# USB-NORA-W1_SCHEM_02.net
KiCad netlist of a schematic drawn in Altium Designer
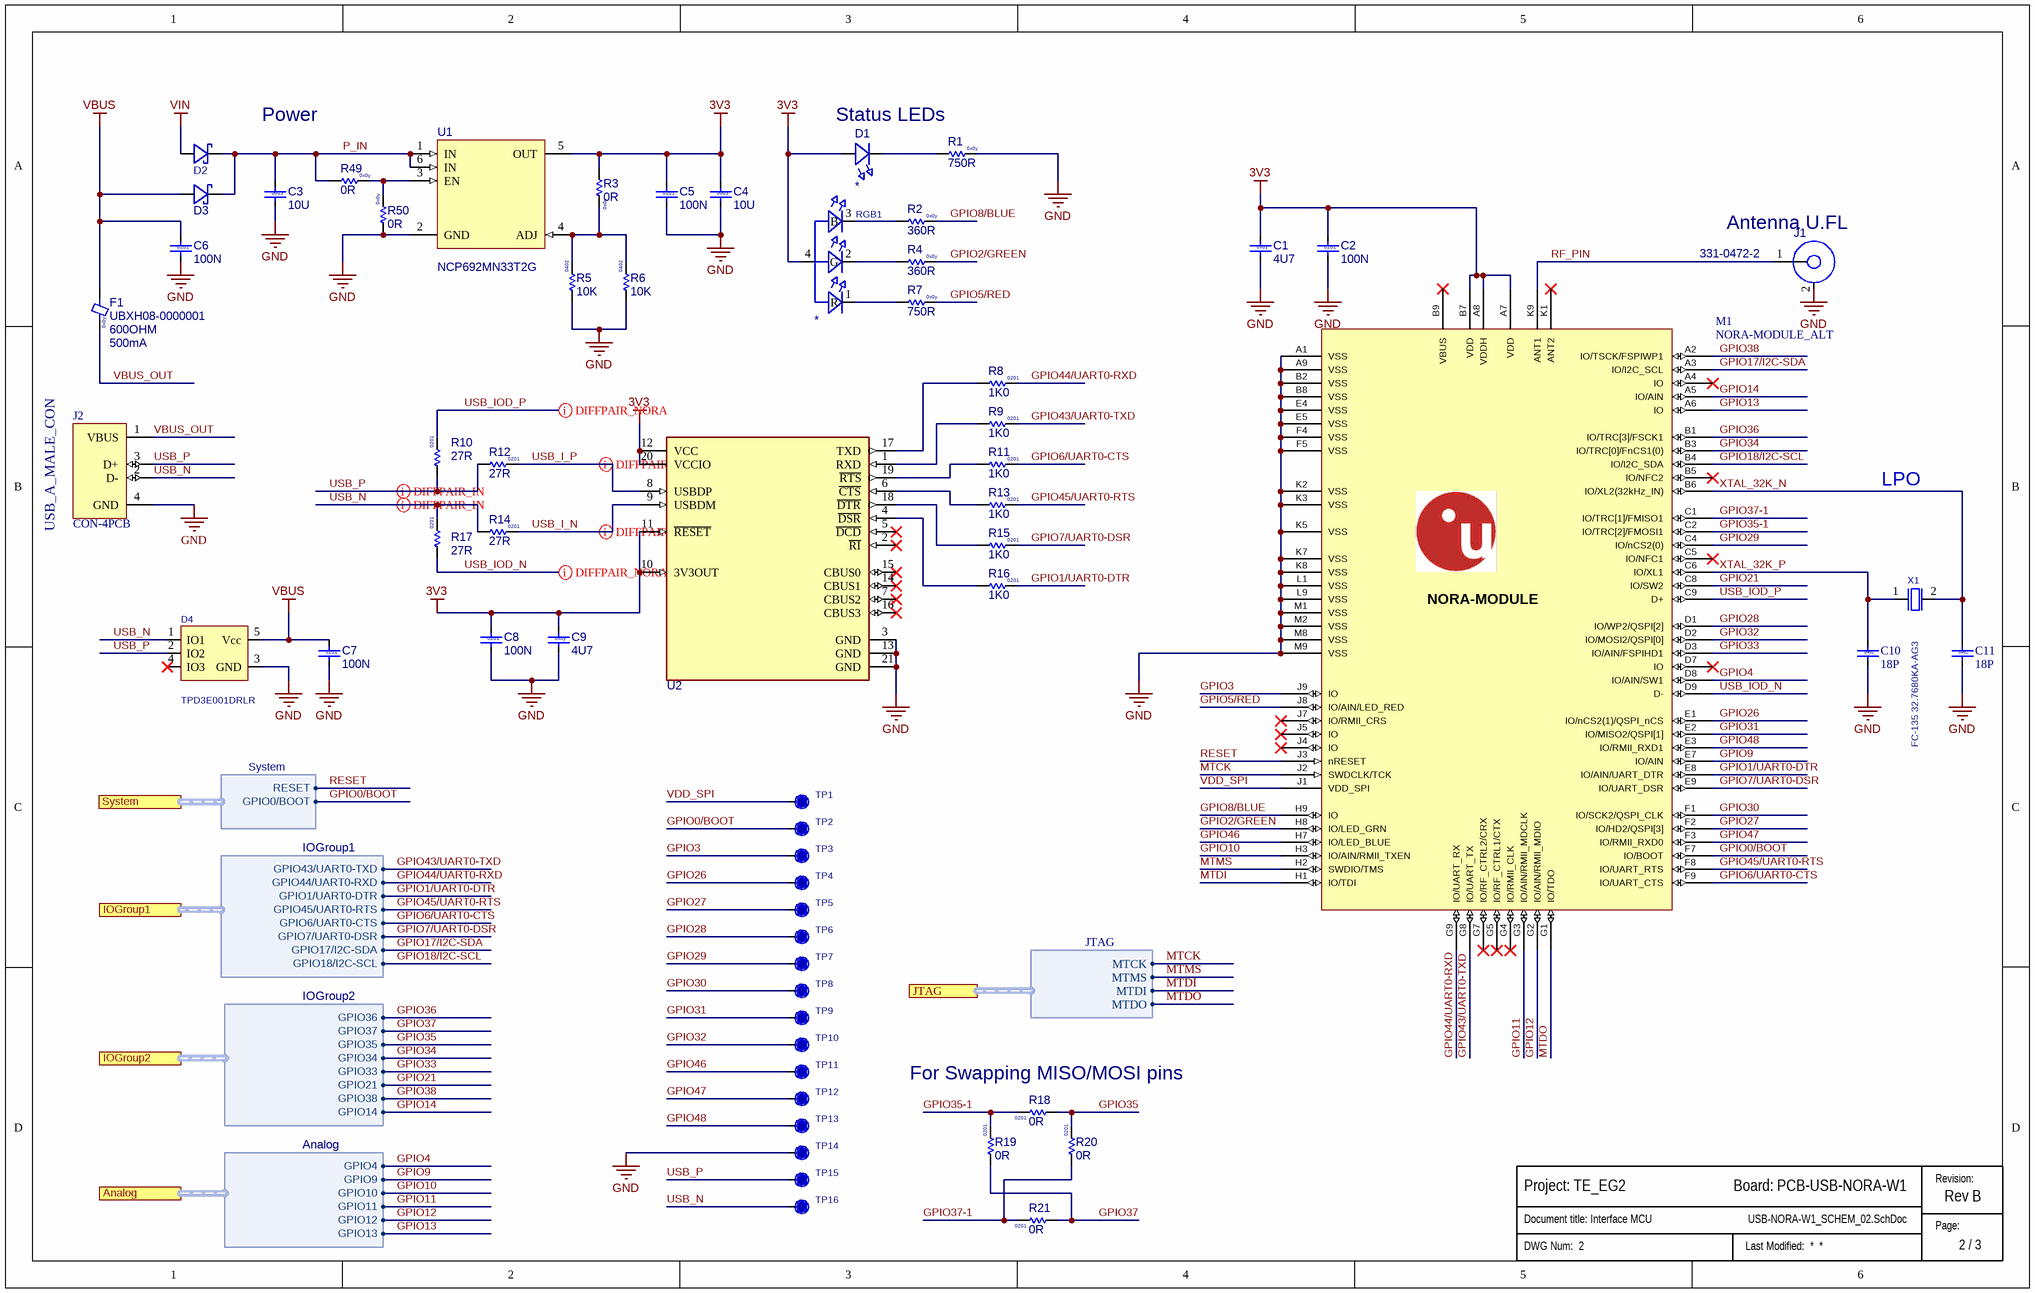
[diagram p0: USB-NORA-W1_SCHEM_02.SchDoc]

(export (version "E")
  (design (tool "Eeschema 10.0.6"))
  (components
    (comp (ref "C1")
      (value "4U7")
      (footprint "Cap 0402 HD")
      (description "CAP CER X5R 0402")
      (fields
        (field (name "SIZE") "0x0y")
        (field (name "PART NUMBER") "UBXH01-0000243")
        (field (name "TOLERANCE") "20%")
        (field (name "EDITOR") "dario.antonaz")
        (field (name "RELEASED BY") "pasquale.scorca")
      )
      (libsource (lib "UBX_Parts_DB_Lib") (part "Cap Chip"))
    )
    (comp (ref "C2")
      (value "100N")
      (footprint "Cap 0201 HD")
      (description "CAP CER X5R 0201 100N 10% 10V")
      (fields
        (field (name "SIZE") "0201")
        (field (name "PART NUMBER") "UBXH01-0000245")
        (field (name "TOLERANCE") "10%")
        (field (name "EDITOR") "dario.antonaz")
        (field (name "RELEASED BY") "jure.podmenik")
      )
      (libsource (lib "UBX_Parts_DB_Lib") (part "Cap Chip"))
    )
    (comp (ref "C3")
      (value "10U")
      (footprint "Cap 0603 HD")
      (description "CAP CER X5R 0603 10U 20% 10V")
      (fields
        (field (name "SIZE") "0603")
        (field (name "PART NUMBER") "UBXH01-0000040")
        (field (name "TOLERANCE") "20%")
        (field (name "EDITOR") "pierpaolo.arban")
        (field (name "RELEASED BY") "matej.budin")
      )
      (libsource (lib "UBX_Parts_DB_Lib") (part "Cap Chip"))
    )
    (comp (ref "C4")
      (value "10U")
      (footprint "Cap 0603 HD")
      (description "CAP CER X5R 0603 10U 20% 10V")
      (fields
        (field (name "SIZE") "0603")
        (field (name "PART NUMBER") "UBXH01-0000040")
        (field (name "TOLERANCE") "20%")
        (field (name "EDITOR") "pierpaolo.arban")
        (field (name "RELEASED BY") "matej.budin")
      )
      (libsource (lib "UBX_Parts_DB_Lib") (part "Cap Chip"))
    )
    (comp (ref "C5")
      (value "100N")
      (footprint "Cap 0201 HD")
      (description "CAP CER X5R 0201 100N 10% 10V")
      (fields
        (field (name "SIZE") "0201")
        (field (name "PART NUMBER") "UBXH01-0000245")
        (field (name "TOLERANCE") "10%")
        (field (name "EDITOR") "dario.antonaz")
        (field (name "RELEASED BY") "jure.podmenik")
      )
      (libsource (lib "UBX_Parts_DB_Lib") (part "Cap Chip"))
    )
    (comp (ref "C6")
      (value "100N")
      (footprint "Cap 0201 HD")
      (description "CAP CER X5R 0201 100N 10% 10V")
      (fields
        (field (name "SIZE") "0201")
        (field (name "PART NUMBER") "UBXH01-0000245")
        (field (name "TOLERANCE") "10%")
        (field (name "EDITOR") "dario.antonaz")
        (field (name "RELEASED BY") "jure.podmenik")
      )
      (libsource (lib "UBX_Parts_DB_Lib") (part "Cap Chip"))
    )
    (comp (ref "C7")
      (value "100N")
      (footprint "Cap 0201 HD")
      (description "CAP CER X5R 0201 100N 10% 10V")
      (fields
        (field (name "SIZE") "0201")
        (field (name "PART NUMBER") "UBXH01-0000245")
        (field (name "TOLERANCE") "10%")
        (field (name "EDITOR") "dario.antonaz")
        (field (name "RELEASED BY") "jure.podmenik")
      )
      (libsource (lib "UBX_Parts_DB_Lib") (part "Cap Chip"))
    )
    (comp (ref "C8")
      (value "100N")
      (footprint "Cap 0201 HD")
      (description "CAP CER X5R 0201 100N 10% 10V")
      (fields
        (field (name "SIZE") "0201")
        (field (name "PART NUMBER") "UBXH01-0000245")
        (field (name "TOLERANCE") "10%")
        (field (name "EDITOR") "dario.antonaz")
        (field (name "RELEASED BY") "jure.podmenik")
      )
      (libsource (lib "UBX_Parts_DB_Lib") (part "Cap Chip"))
    )
    (comp (ref "C9")
      (value "4U7")
      (footprint "Cap 0402 HD")
      (description "CAP CER X5R 0402")
      (fields
        (field (name "SIZE") "0x0y")
        (field (name "PART NUMBER") "UBXH01-0000243")
        (field (name "TOLERANCE") "20%")
        (field (name "EDITOR") "dario.antonaz")
        (field (name "RELEASED BY") "pasquale.scorca")
      )
      (libsource (lib "UBX_Parts_DB_Lib") (part "Cap Chip"))
    )
    (comp (ref "C10")
      (value "18P")
      (footprint "Cap 0402")
      (description "CAP CER C0G 0402 18P 5% 25V")
      (fields
        (field (name "SIZE") "0402")
        (field (name "PART NUMBER") "UBXH01-0004017")
        (field (name "TOLERANCE") "5%")
        (field (name "EDITOR") "doris.zahnd")
        (field (name "RELEASED BY") "daniel.hurni")
      )
      (libsource (lib "UBX_Parts_DB_Lib") (part "Cap Chip"))
    )
    (comp (ref "C11")
      (value "18P")
      (footprint "Cap 0402")
      (description "CAP CER C0G 0402 18P 5% 25V")
      (fields
        (field (name "SIZE") "0402")
        (field (name "PART NUMBER") "UBXH01-0004017")
        (field (name "TOLERANCE") "5%")
        (field (name "EDITOR") "doris.zahnd")
        (field (name "RELEASED BY") "daniel.hurni")
      )
      (libsource (lib "UBX_Parts_DB_Lib") (part "Cap Chip"))
    )
    (comp (ref "D1")
      (value "UBXH11-0000018")
      (footprint "LED-0603")
      (description "LED CHIP 0603 LOW CURRENT OSRAM 0.002A")
      (fields
        (field (name "COLOR") "*")
        (field (name "MANUFACTURER") "Osram")
        (field (name "EDITOR") "johann.furrer")
        (field (name "RELEASED BY") "martin.grasse")
      )
      (libsource (lib "UBX_Parts_DB_Lib") (part "LED_BASE"))
    )
    (comp (ref "D2")
      (value "110-00005")
      (footprint "SOD-123F_U")
      (description "Diode, Schottky, 20V 1A SOD-123F, 340mV Vf @ 1A\nMBR120VLSFT3G")
      (fields (field (name "VOLTAGE") "20V"))
      (libsource (lib "Arena_Parts_DB_Lib") (part "Diode_Schottky"))
    )
    (comp (ref "D3")
      (value "110-00005")
      (footprint "SOD-123F_U")
      (description "Diode, Schottky, 20V 1A SOD-123F, 340mV Vf @ 1A\nMBR120VLSFT3G")
      (fields (field (name "VOLTAGE") "20V"))
      (libsource (lib "Arena_Parts_DB_Lib") (part "Diode_Schottky"))
    )
    (comp (ref "D4")
      (value "110-00018")
      (footprint "SOT-553")
      (description "LOW-CAPACITANCE 3-CHANNEL ESD-PROTECTION ARRAY")
      (fields
        (field (name "MANUFACTURER P/N") "TPD3E001DRLR")
        (field (name "MANUFACTURER") "Texas Instruments")
        (field (name "VOLTAGE") "5V")
      )
      (libsource (lib "Arena_Parts_DB_Lib") (part "TPD3E001"))
    )
    (comp (ref "F1")
      (value "600OHM")
      (footprint "IND 0603 HD")
      (description "FERRITE BEAD, 0603, 600 OHM AT 100MHZ")
      (fields
        (field (name "SIZE") "0x0y")
        (field (name "PART NUMBER") "UBXH08-0000001")
        (field (name "MAX CURRENT") "500mA")
        (field (name "MANUFACTURER") "TDK Corporation")
        (field (name "Comment") "UBXH08-0000001")
        (field (name "EDITOR") "daniel.hurni")
        (field (name "RELEASED BY") "martin.frauchiger")
      )
      (libsource (lib "UBX_Parts_DB_Lib") (part "FB sm"))
    )
    (comp (ref "J1")
      (value "UBXH04-0001026")
      (footprint "U.FL_3Pin")
      (description "CONN HIROSE U.FL SERIES STRAIGHT RECEPTACLE")
      (fields
        (field (name "MANUFACTURER P/N") "331-0472-2")
        (field (name "MANUFACTURER") "Hirose")
        (field (name "EDITOR") "roland.rust")
        (field (name "RELEASED BY") "roland.rust")
      )
      (libsource (lib "UBX_Parts_DB_Lib") (part "CON_Coax_2Pin"))
    )
    (comp (ref "J2")
      (value "CON-4PCB")
      (footprint "USB-A-PCB")
      (description "CONN USB PLUG A TYPE PCB FOOTPRINT")
      (fields (field (name "PART NUMBER") "UBXH04-0000711") (field (name "EDITOR") "aneeb.sohail"))
      (libsource (lib "UBX_Parts_DB_Lib") (part "CON-4PCB"))
    )
    (comp (ref "M1")
      (value "NORA-MODULE_ALT")
      (footprint "NORA:NORA_LGA82R_1430X1040X180_ANT")
      (description "u-blox NORA module generic symbol for use within module designs - alternate version")
      (fields (field (name "PART NUMBER") "NORA") (field (name "MANUFACTURER") "u-blox"))
      (libsource (lib "NORA") (part "NORA-MODULE_ALT"))
    )
    (comp (ref "R1")
      (value "750R")
      (footprint "RES 0402 HD")
      (description "RES THICK FILM CHIP 0402")
      (fields
        (field (name "SIZE") "0x0y")
        (field (name "PART NUMBER") "UBXH18-0008046")
        (field (name "TOLERANCE") "5%")
        (field (name "EDITOR") "jaka.bevk")
        (field (name "RELEASED BY") "erian.bezhani")
      )
      (libsource (lib "UBX_Parts_DB_Lib") (part "Res sm"))
    )
    (comp (ref "R2")
      (value "360R")
      (footprint "RES 0402 HD")
      (description "RES THICK FILM CHIP 0402")
      (fields
        (field (name "SIZE") "0x0y")
        (field (name "PART NUMBER") "UBXH18-0000216")
        (field (name "TOLERANCE") "1%")
        (field (name "EDITOR") "michael.hein")
        (field (name "RELEASED BY") "vasyl.dykyy")
      )
      (libsource (lib "UBX_Parts_DB_Lib") (part "Res sm"))
    )
    (comp (ref "R3")
      (value "0R")
      (footprint "RES 0402 HD")
      (description "RES THICK FILM CHIP 0402")
      (fields
        (field (name "SIZE") "0x0y")
        (field (name "PART NUMBER") "UBXH18-0003002")
        (field (name "TOLERANCE") "0")
        (field (name "EDITOR") "charlotte.biber")
        (field (name "RELEASED BY") "peter.mueller")
      )
      (libsource (lib "UBX_Parts_DB_Lib") (part "Res sm"))
    )
    (comp (ref "R4")
      (value "360R")
      (footprint "RES 0402 HD")
      (description "RES THICK FILM CHIP 0402")
      (fields
        (field (name "SIZE") "0x0y")
        (field (name "PART NUMBER") "UBXH18-0000216")
        (field (name "TOLERANCE") "1%")
        (field (name "EDITOR") "michael.hein")
        (field (name "RELEASED BY") "vasyl.dykyy")
      )
      (libsource (lib "UBX_Parts_DB_Lib") (part "Res sm"))
    )
    (comp (ref "R5")
      (value "10K")
      (footprint "RES 0402 HD")
      (description "RES THICK FILM CHIP 0402 10K 5% 100mW")
      (fields
        (field (name "SIZE") "0402")
        (field (name "PART NUMBER") "UBXH18-0008073")
        (field (name "TOLERANCE") "5%")
        (field (name "EDITOR") "martin.frauchiger")
        (field (name "RELEASED BY") "martin.frauchiger")
      )
      (libsource (lib "UBX_Parts_DB_Lib") (part "Res sm"))
    )
    (comp (ref "R6")
      (value "10K")
      (footprint "RES 0402 HD")
      (description "RES THICK FILM CHIP 0402 10K 5% 100mW")
      (fields
        (field (name "SIZE") "0402")
        (field (name "PART NUMBER") "UBXH18-0008073")
        (field (name "TOLERANCE") "5%")
        (field (name "EDITOR") "martin.frauchiger")
        (field (name "RELEASED BY") "martin.frauchiger")
      )
      (libsource (lib "UBX_Parts_DB_Lib") (part "Res sm"))
    )
    (comp (ref "R7")
      (value "750R")
      (footprint "RES 0402 HD")
      (description "RES THICK FILM CHIP 0402")
      (fields
        (field (name "SIZE") "0x0y")
        (field (name "PART NUMBER") "UBXH18-0008046")
        (field (name "TOLERANCE") "5%")
        (field (name "EDITOR") "jaka.bevk")
        (field (name "RELEASED BY") "erian.bezhani")
      )
      (libsource (lib "UBX_Parts_DB_Lib") (part "Res sm"))
    )
    (comp (ref "R8")
      (value "1K0")
      (footprint "RES 0201 HD")
      (description "RES THICK FILM CHIP 0201 1K0 5% 50mW")
      (fields
        (field (name "SIZE") "0201")
        (field (name "PART NUMBER") "UBXH18-0000007")
        (field (name "TOLERANCE") "5%")
        (field (name "EDITOR") "martin.pilik")
        (field (name "RELEASED BY") "fabrice.bret-dibat")
      )
      (libsource (lib "UBX_Parts_DB_Lib") (part "Res sm"))
    )
    (comp (ref "R9")
      (value "1K0")
      (footprint "RES 0201 HD")
      (description "RES THICK FILM CHIP 0201 1K0 5% 50mW")
      (fields
        (field (name "SIZE") "0201")
        (field (name "PART NUMBER") "UBXH18-0000007")
        (field (name "TOLERANCE") "5%")
        (field (name "EDITOR") "martin.pilik")
        (field (name "RELEASED BY") "fabrice.bret-dibat")
      )
      (libsource (lib "UBX_Parts_DB_Lib") (part "Res sm"))
    )
    (comp (ref "R10")
      (value "27R")
      (footprint "RES 0201 HD")
      (description "RES THICK FILM CHIP 0201 27R 5% 50mW")
      (fields
        (field (name "SIZE") "0201")
        (field (name "PART NUMBER") "UBXH18-0000470")
        (field (name "TOLERANCE") "5%")
        (field (name "EDITOR") "alex.claville")
        (field (name "RELEASED BY") "andre.pick")
      )
      (libsource (lib "UBX_Parts_DB_Lib") (part "Res sm"))
    )
    (comp (ref "R11")
      (value "1K0")
      (footprint "RES 0201 HD")
      (description "RES THICK FILM CHIP 0201 1K0 5% 50mW")
      (fields
        (field (name "SIZE") "0201")
        (field (name "PART NUMBER") "UBXH18-0000007")
        (field (name "TOLERANCE") "5%")
        (field (name "EDITOR") "martin.pilik")
        (field (name "RELEASED BY") "fabrice.bret-dibat")
      )
      (libsource (lib "UBX_Parts_DB_Lib") (part "Res sm"))
    )
    (comp (ref "R12")
      (value "27R")
      (footprint "RES 0201 HD")
      (description "RES THICK FILM CHIP 0201 27R 5% 50mW")
      (fields
        (field (name "SIZE") "0201")
        (field (name "PART NUMBER") "UBXH18-0000470")
        (field (name "TOLERANCE") "5%")
        (field (name "EDITOR") "alex.claville")
        (field (name "RELEASED BY") "andre.pick")
      )
      (libsource (lib "UBX_Parts_DB_Lib") (part "Res sm"))
    )
    (comp (ref "R13")
      (value "1K0")
      (footprint "RES 0201 HD")
      (description "RES THICK FILM CHIP 0201 1K0 5% 50mW")
      (fields
        (field (name "SIZE") "0201")
        (field (name "PART NUMBER") "UBXH18-0000007")
        (field (name "TOLERANCE") "5%")
        (field (name "EDITOR") "martin.pilik")
        (field (name "RELEASED BY") "fabrice.bret-dibat")
      )
      (libsource (lib "UBX_Parts_DB_Lib") (part "Res sm"))
    )
    (comp (ref "R14")
      (value "27R")
      (footprint "RES 0201 HD")
      (description "RES THICK FILM CHIP 0201 27R 5% 50mW")
      (fields
        (field (name "SIZE") "0201")
        (field (name "PART NUMBER") "UBXH18-0000470")
        (field (name "TOLERANCE") "5%")
        (field (name "EDITOR") "alex.claville")
        (field (name "RELEASED BY") "andre.pick")
      )
      (libsource (lib "UBX_Parts_DB_Lib") (part "Res sm"))
    )
    (comp (ref "R15")
      (value "1K0")
      (footprint "RES 0201 HD")
      (description "RES THICK FILM CHIP 0201 1K0 5% 50mW")
      (fields
        (field (name "SIZE") "0201")
        (field (name "PART NUMBER") "UBXH18-0000007")
        (field (name "TOLERANCE") "5%")
        (field (name "EDITOR") "martin.pilik")
        (field (name "RELEASED BY") "fabrice.bret-dibat")
      )
      (libsource (lib "UBX_Parts_DB_Lib") (part "Res sm"))
    )
    (comp (ref "R16")
      (value "1K0")
      (footprint "RES 0201 HD")
      (description "RES THICK FILM CHIP 0201 1K0 5% 50mW")
      (fields
        (field (name "SIZE") "0201")
        (field (name "PART NUMBER") "UBXH18-0000007")
        (field (name "TOLERANCE") "5%")
        (field (name "EDITOR") "martin.pilik")
        (field (name "RELEASED BY") "fabrice.bret-dibat")
      )
      (libsource (lib "UBX_Parts_DB_Lib") (part "Res sm"))
    )
    (comp (ref "R17")
      (value "27R")
      (footprint "RES 0201 HD")
      (description "RES THICK FILM CHIP 0201 27R 5% 50mW")
      (fields
        (field (name "SIZE") "0201")
        (field (name "PART NUMBER") "UBXH18-0000470")
        (field (name "TOLERANCE") "5%")
        (field (name "EDITOR") "alex.claville")
        (field (name "RELEASED BY") "andre.pick")
      )
      (libsource (lib "UBX_Parts_DB_Lib") (part "Res sm"))
    )
    (comp (ref "R18")
      (value "0R")
      (footprint "RES 0201 HD")
      (description "RES THICK FILM CHIP 0201 0R 0 500mA")
      (fields
        (field (name "SIZE") "0201")
        (field (name "PART NUMBER") "UBXH18-0003003")
        (field (name "TOLERANCE") "0")
        (field (name "EDITOR") "martin.pilik")
        (field (name "RELEASED BY") "fabrice.bret-dibat")
      )
      (libsource (lib "") (part "Res sm_1"))
    )
    (comp (ref "R19")
      (value "0R")
      (footprint "RES 0201 HD")
      (description "RES THICK FILM CHIP 0201 0R 0 500mA")
      (fields
        (field (name "SIZE") "0201")
        (field (name "PART NUMBER") "UBXH18-0003003")
        (field (name "TOLERANCE") "0")
        (field (name "EDITOR") "martin.pilik")
        (field (name "RELEASED BY") "fabrice.bret-dibat")
      )
      (libsource (lib "UBX_Parts_DB_Lib") (part "Res sm"))
    )
    (comp (ref "R20")
      (value "0R")
      (footprint "RES 0201 HD")
      (description "RES THICK FILM CHIP 0201 0R 0 500mA")
      (fields
        (field (name "SIZE") "0201")
        (field (name "PART NUMBER") "UBXH18-0003003")
        (field (name "TOLERANCE") "0")
        (field (name "EDITOR") "martin.pilik")
        (field (name "RELEASED BY") "fabrice.bret-dibat")
      )
      (libsource (lib "UBX_Parts_DB_Lib") (part "Res sm"))
    )
    (comp (ref "R21")
      (value "0R")
      (footprint "RES 0201 HD")
      (description "RES THICK FILM CHIP 0201 0R 0 500mA")
      (fields
        (field (name "SIZE") "0201")
        (field (name "PART NUMBER") "UBXH18-0003003")
        (field (name "TOLERANCE") "0")
        (field (name "EDITOR") "martin.pilik")
        (field (name "RELEASED BY") "fabrice.bret-dibat")
      )
      (libsource (lib "") (part "Res sm_1"))
    )
    (comp (ref "R49")
      (value "0R")
      (footprint "RES 0402 HD")
      (description "RES THICK FILM CHIP 0402")
      (fields
        (field (name "SIZE") "0x0y")
        (field (name "PART NUMBER") "UBXH18-0003002")
        (field (name "TOLERANCE") "0")
        (field (name "EDITOR") "charlotte.biber")
        (field (name "RELEASED BY") "peter.mueller")
      )
      (libsource (lib "UBX_Parts_DB_Lib") (part "Res sm"))
    )
    (comp (ref "R50")
      (value "0R")
      (footprint "RES 0402 HD")
      (description "RES THICK FILM CHIP 0402")
      (fields
        (field (name "SIZE") "0x0y")
        (field (name "PART NUMBER") "UBXH18-0003002")
        (field (name "TOLERANCE") "0")
        (field (name "EDITOR") "charlotte.biber")
        (field (name "RELEASED BY") "peter.mueller")
      )
      (libsource (lib "UBX_Parts_DB_Lib") (part "Res sm"))
    )
    (comp (ref "RGB1")
      (value "115-00026")
      (footprint "LED_1616")
      (description "LED RGB SMT 0606")
      (fields (field (name "COLOR") "*") (field (name "VOLTAGE") "None"))
      (libsource (lib "Arena_Parts_DB_Lib") (part "LED_RGB_CA_4"))
    )
    (comp (ref "TP1")
      (value "TP")
      (footprint "TP10R")
      (description "Testpoint, Round 1.0mm Dia")
      (fields
        (field (name "PART NUMBER") "TP10R")
        (field (name "ADDED BY") "Jeremy D")
        (field (name "CHECKED BY") "Paul B")
      )
      (libsource (lib "LEGACY_Rigado_AltiumLib") (part "TP_R"))
    )
    (comp (ref "TP2")
      (value "TP")
      (footprint "TP10R")
      (description "Testpoint, Round 1.0mm Dia")
      (fields
        (field (name "PART NUMBER") "TP10R")
        (field (name "ADDED BY") "Jeremy D")
        (field (name "CHECKED BY") "Paul B")
      )
      (libsource (lib "LEGACY_Rigado_AltiumLib") (part "TP_R"))
    )
    (comp (ref "TP3")
      (value "TP")
      (footprint "TP10R")
      (description "Testpoint, Round 1.0mm Dia")
      (fields
        (field (name "PART NUMBER") "TP10R")
        (field (name "ADDED BY") "Jeremy D")
        (field (name "CHECKED BY") "Paul B")
      )
      (libsource (lib "LEGACY_Rigado_AltiumLib") (part "TP_R"))
    )
    (comp (ref "TP4")
      (value "TP")
      (footprint "TP10R")
      (description "Testpoint, Round 1.0mm Dia")
      (fields
        (field (name "PART NUMBER") "TP10R")
        (field (name "ADDED BY") "Jeremy D")
        (field (name "CHECKED BY") "Paul B")
      )
      (libsource (lib "LEGACY_Rigado_AltiumLib") (part "TP_R"))
    )
    (comp (ref "TP5")
      (value "TP")
      (footprint "TP10R")
      (description "Testpoint, Round 1.0mm Dia")
      (fields
        (field (name "PART NUMBER") "TP10R")
        (field (name "ADDED BY") "Jeremy D")
        (field (name "CHECKED BY") "Paul B")
      )
      (libsource (lib "LEGACY_Rigado_AltiumLib") (part "TP_R"))
    )
    (comp (ref "TP6")
      (value "TP")
      (footprint "TP10R")
      (description "Testpoint, Round 1.0mm Dia")
      (fields
        (field (name "PART NUMBER") "TP10R")
        (field (name "ADDED BY") "Jeremy D")
        (field (name "CHECKED BY") "Paul B")
      )
      (libsource (lib "LEGACY_Rigado_AltiumLib") (part "TP_R"))
    )
    (comp (ref "TP7")
      (value "TP")
      (footprint "TP10R")
      (description "Testpoint, Round 1.0mm Dia")
      (fields
        (field (name "PART NUMBER") "TP10R")
        (field (name "ADDED BY") "Jeremy D")
        (field (name "CHECKED BY") "Paul B")
      )
      (libsource (lib "LEGACY_Rigado_AltiumLib") (part "TP_R"))
    )
    (comp (ref "TP8")
      (value "TP")
      (footprint "TP10R")
      (description "Testpoint, Round 1.0mm Dia")
      (fields
        (field (name "PART NUMBER") "TP10R")
        (field (name "ADDED BY") "Jeremy D")
        (field (name "CHECKED BY") "Paul B")
      )
      (libsource (lib "LEGACY_Rigado_AltiumLib") (part "TP_R"))
    )
    (comp (ref "TP9")
      (value "TP")
      (footprint "TP10R")
      (description "Testpoint, Round 1.0mm Dia")
      (fields
        (field (name "PART NUMBER") "TP10R")
        (field (name "ADDED BY") "Jeremy D")
        (field (name "CHECKED BY") "Paul B")
      )
      (libsource (lib "LEGACY_Rigado_AltiumLib") (part "TP_R"))
    )
    (comp (ref "TP10")
      (value "TP")
      (footprint "TP10R")
      (description "Testpoint, Round 1.0mm Dia")
      (fields
        (field (name "PART NUMBER") "TP10R")
        (field (name "ADDED BY") "Jeremy D")
        (field (name "CHECKED BY") "Paul B")
      )
      (libsource (lib "LEGACY_Rigado_AltiumLib") (part "TP_R"))
    )
    (comp (ref "TP11")
      (value "TP")
      (footprint "TP10R")
      (description "Testpoint, Round 1.0mm Dia")
      (fields
        (field (name "PART NUMBER") "TP10R")
        (field (name "ADDED BY") "Jeremy D")
        (field (name "CHECKED BY") "Paul B")
      )
      (libsource (lib "LEGACY_Rigado_AltiumLib") (part "TP_R"))
    )
    (comp (ref "TP12")
      (value "TP")
      (footprint "TP10R")
      (description "Testpoint, Round 1.0mm Dia")
      (fields
        (field (name "PART NUMBER") "TP10R")
        (field (name "ADDED BY") "Jeremy D")
        (field (name "CHECKED BY") "Paul B")
      )
      (libsource (lib "LEGACY_Rigado_AltiumLib") (part "TP_R"))
    )
    (comp (ref "TP13")
      (value "TP")
      (footprint "TP10R")
      (description "Testpoint, Round 1.0mm Dia")
      (fields
        (field (name "PART NUMBER") "TP10R")
        (field (name "ADDED BY") "Jeremy D")
        (field (name "CHECKED BY") "Paul B")
      )
      (libsource (lib "LEGACY_Rigado_AltiumLib") (part "TP_R"))
    )
    (comp (ref "TP14")
      (value "TP")
      (footprint "TP10R")
      (description "Testpoint, Round 1.0mm Dia")
      (fields
        (field (name "PART NUMBER") "TP10R")
        (field (name "ADDED BY") "Jeremy D")
        (field (name "CHECKED BY") "Paul B")
      )
      (libsource (lib "LEGACY_Rigado_AltiumLib") (part "TP_R"))
    )
    (comp (ref "TP15")
      (value "TP")
      (footprint "TP10R")
      (description "Testpoint, Round 1.0mm Dia")
      (fields
        (field (name "PART NUMBER") "TP10R")
        (field (name "ADDED BY") "Jeremy D")
        (field (name "CHECKED BY") "Paul B")
      )
      (libsource (lib "LEGACY_Rigado_AltiumLib") (part "TP_R"))
    )
    (comp (ref "TP16")
      (value "TP")
      (footprint "TP10R")
      (description "Testpoint, Round 1.0mm Dia")
      (fields
        (field (name "PART NUMBER") "TP10R")
        (field (name "ADDED BY") "Jeremy D")
        (field (name "CHECKED BY") "Paul B")
      )
      (libsource (lib "LEGACY_Rigado_AltiumLib") (part "TP_R"))
    )
    (comp (ref "U1")
      (value "NCP692MN33T2G")
      (footprint "DFN-PSON.1P3X3-7pin_HS-7N")
      (description "LOW DROPOUT REGULATOR ON SEMICONDUCTOR NCP692MN33T2G 6DFN 3.3V 6V 1A")
      (fields
        (field (name "PART NUMBER") "UBXH12-0000459")
        (field (name "MANUFACTURER") "ON Semiconductor")
        (field (name "EDITOR") "hakan.ekfors")
        (field (name "RELEASED BY") "markus.wejrot")
      )
      (libsource (lib "UBX_Parts_DB_Lib") (part "NCP692MN33T2G"))
    )
    (comp (ref "U2")
      (value "FT231XQ-R")
      (footprint "QFN_5x5_FT231XQ")
      (description "FTDI USB TO SERIAL FULL UART INTERFACE QFN20")
      (fields
        (field (name "PART NUMBER") "UBXH10-0000054")
        (field (name "MANUFACTURER") "FTDI Future Technology Devices International")
        (field (name "EDITOR") "adam.johansson")
      )
      (libsource (lib "UBX_Parts_DB_Lib") (part "FT231XQ-R"))
    )
    (comp (ref "X1")
      (value "100-00005")
      (footprint "XTAL_3215")
      (description "XTAL, 2Pin, 32.768kHz, 7pF 20ppm")
      (fields (field (name "MANUFACTURER P/N") "FC-135 32.7680KA-AG3") (field (name "MANUFACTURER") "Epson"))
      (libsource (lib "Arena_Parts_DB_Lib") (part "XTAL_2Pin"))
    )
  )
  (nets
    (net (code "7") (name "/GPIO0{slash}BOOT") (class "Default")
      (node (ref "M1") (pin "F7") (pinfunction "IO/BOOT_F7") (pintype "bidirectional"))
      (node (ref "TP2") (pin "1") (pintype "passive"))
    )
    (net (code "8") (name "/GPIO1{slash}UART0-DTR") (class "Default")
      (node (ref "M1") (pin "E8") (pinfunction "IO/AIN/UART_DTR_E8") (pintype "bidirectional"))
      (node (ref "R16") (pin "2") (pinfunction "2_2") (pintype "passive"))
    )
    (net (code "9") (name "/GPIO2{slash}GREEN") (class "Default")
      (node (ref "M1") (pin "H8") (pinfunction "IO/LED_GRN_H8") (pintype "bidirectional"))
      (node (ref "R4") (pin "2") (pinfunction "2_2") (pintype "passive"))
    )
    (net (code "10") (name "/GPIO3") (class "Default")
      (node (ref "M1") (pin "J9") (pinfunction "IO_J9") (pintype "bidirectional"))
      (node (ref "TP3") (pin "1") (pintype "passive"))
    )
    (net (code "11") (name "/GPIO4") (class "Default")
      (node (ref "M1") (pin "D8") (pinfunction "IO/AIN/SW1_D8") (pintype "bidirectional"))
    )
    (net (code "12") (name "/GPIO5{slash}RED") (class "Default")
      (node (ref "M1") (pin "J8") (pinfunction "IO/AIN/LED_RED_J8") (pintype "bidirectional"))
      (node (ref "R7") (pin "2") (pinfunction "2_2") (pintype "passive"))
    )
    (net (code "13") (name "/GPIO6{slash}UART0-CTS") (class "Default")
      (node (ref "M1") (pin "F9") (pinfunction "IO/UART_CTS_F9") (pintype "bidirectional"))
      (node (ref "R11") (pin "2") (pinfunction "2_2") (pintype "passive"))
    )
    (net (code "14") (name "/GPIO7{slash}UART0-DSR") (class "Default")
      (node (ref "M1") (pin "E9") (pinfunction "IO/UART_DSR_E9") (pintype "bidirectional"))
      (node (ref "R15") (pin "2") (pinfunction "2_2") (pintype "passive"))
    )
    (net (code "15") (name "/GPIO8{slash}BLUE") (class "Default")
      (node (ref "M1") (pin "H9") (pinfunction "IO_H9") (pintype "bidirectional"))
      (node (ref "R2") (pin "2") (pinfunction "2_2") (pintype "passive"))
    )
    (net (code "16") (name "/GPIO9") (class "Default")
      (node (ref "M1") (pin "E7") (pinfunction "IO/AIN_E7") (pintype "bidirectional"))
    )
    (net (code "17") (name "/GPIO10") (class "Default")
      (node (ref "M1") (pin "H3") (pinfunction "IO/AIN/RMII_TXEN_H3") (pintype "bidirectional"))
    )
    (net (code "18") (name "/GPIO11") (class "Default")
      (node (ref "M1") (pin "G3") (pinfunction "IO/AIN/RMII_MDCLK_G3") (pintype "bidirectional"))
    )
    (net (code "19") (name "/GPIO12") (class "Default")
      (node (ref "M1") (pin "G2") (pinfunction "IO/AIN/RMII_MDIO_G2") (pintype "bidirectional"))
    )
    (net (code "20") (name "/GPIO13") (class "Default")
      (node (ref "M1") (pin "A6") (pinfunction "IO_A6") (pintype "bidirectional"))
    )
    (net (code "21") (name "/GPIO14") (class "Default")
      (node (ref "M1") (pin "A5") (pinfunction "IO/AIN_A5") (pintype "bidirectional"))
    )
    (net (code "22") (name "/GPIO17{slash}I2C-SDA") (class "Default")
      (node (ref "M1") (pin "A3") (pinfunction "IO/I2C_SCL_A3") (pintype "bidirectional"))
    )
    (net (code "23") (name "/GPIO18{slash}I2C-SCL") (class "Default")
      (node (ref "M1") (pin "B4") (pinfunction "IO/I2C_SDA_B4") (pintype "bidirectional"))
    )
    (net (code "24") (name "/GPIO21") (class "Default")
      (node (ref "M1") (pin "C8") (pinfunction "IO/SW2_C8") (pintype "bidirectional"))
    )
    (net (code "25") (name "/GPIO26") (class "Default")
      (node (ref "M1") (pin "E1") (pinfunction "IO/nCS2(1)/QSPI_nCS_E1") (pintype "bidirectional"))
      (node (ref "TP4") (pin "1") (pintype "passive"))
    )
    (net (code "26") (name "/GPIO27") (class "Default")
      (node (ref "M1") (pin "F2") (pinfunction "IO/HD2/QSPI[3]_F2") (pintype "bidirectional"))
      (node (ref "TP5") (pin "1") (pintype "passive"))
    )
    (net (code "27") (name "/GPIO28") (class "Default")
      (node (ref "M1") (pin "D1") (pinfunction "IO/WP2/QSPI[2]_D1") (pintype "bidirectional"))
      (node (ref "TP6") (pin "1") (pintype "passive"))
    )
    (net (code "28") (name "/GPIO29") (class "Default")
      (node (ref "M1") (pin "C4") (pinfunction "IO/nCS2(0)_C4") (pintype "bidirectional"))
      (node (ref "TP7") (pin "1") (pintype "passive"))
    )
    (net (code "29") (name "/GPIO30") (class "Default")
      (node (ref "M1") (pin "F1") (pinfunction "IO/SCK2/QSPI_CLK_F1") (pintype "bidirectional"))
      (node (ref "TP8") (pin "1") (pintype "passive"))
    )
    (net (code "30") (name "/GPIO31") (class "Default")
      (node (ref "M1") (pin "E2") (pinfunction "IO/MISO2/QSPI[1]_E2") (pintype "bidirectional"))
      (node (ref "TP9") (pin "1") (pintype "passive"))
    )
    (net (code "31") (name "/GPIO32") (class "Default")
      (node (ref "M1") (pin "D2") (pinfunction "IO/MOSI2/QSPI[0]_D2") (pintype "bidirectional"))
      (node (ref "TP10") (pin "1") (pintype "passive"))
    )
    (net (code "32") (name "/GPIO33") (class "Default")
      (node (ref "M1") (pin "D3") (pinfunction "IO/AIN/FSPIHD1_D3") (pintype "bidirectional"))
    )
    (net (code "33") (name "/GPIO34") (class "Default")
      (node (ref "M1") (pin "B3") (pinfunction "IO/TRC[0]/FnCS1(0)_B3") (pintype "bidirectional"))
    )
    (net (code "34") (name "/GPIO35") (class "Default")
      (node (ref "R18") (pin "2") (pinfunction "2_2") (pintype "passive"))
      (node (ref "R20") (pin "2") (pinfunction "2_2") (pintype "passive"))
    )
    (net (code "35") (name "/GPIO35-1") (class "Default")
      (node (ref "M1") (pin "C2") (pinfunction "IO/TRC[2]/FMOSI1_C2") (pintype "bidirectional"))
      (node (ref "R18") (pin "1") (pinfunction "1_1") (pintype "passive"))
      (node (ref "R19") (pin "2") (pinfunction "2_2") (pintype "passive"))
    )
    (net (code "36") (name "/GPIO36") (class "Default")
      (node (ref "M1") (pin "B1") (pinfunction "IO/TRC[3]/FSCK1_B1") (pintype "bidirectional"))
    )
    (net (code "37") (name "/GPIO37") (class "Default")
      (node (ref "R19") (pin "1") (pinfunction "1_1") (pintype "passive"))
      (node (ref "R21") (pin "2") (pinfunction "2_2") (pintype "passive"))
    )
    (net (code "38") (name "/GPIO37-1") (class "Default")
      (node (ref "M1") (pin "C1") (pinfunction "IO/TRC[1]/FMISO1_C1") (pintype "bidirectional"))
      (node (ref "R20") (pin "1") (pinfunction "1_1") (pintype "passive"))
      (node (ref "R21") (pin "1") (pinfunction "1_1") (pintype "passive"))
    )
    (net (code "39") (name "/GPIO38") (class "Default")
      (node (ref "M1") (pin "A2") (pinfunction "IO/TSCK/FSPIWP1_A2") (pintype "bidirectional"))
    )
    (net (code "40") (name "/GPIO43{slash}UART0-TXD") (class "Default")
      (node (ref "M1") (pin "G8") (pinfunction "IO/UART_TX_G8") (pintype "bidirectional"))
      (node (ref "R9") (pin "2") (pinfunction "2_2") (pintype "passive"))
    )
    (net (code "41") (name "/GPIO44{slash}UART0-RXD") (class "Default")
      (node (ref "M1") (pin "G9") (pinfunction "IO/UART_RX_G9") (pintype "bidirectional"))
      (node (ref "R8") (pin "2") (pinfunction "2_2") (pintype "passive"))
    )
    (net (code "42") (name "/GPIO45{slash}UART0-RTS") (class "Default")
      (node (ref "M1") (pin "F8") (pinfunction "IO/UART_RTS_F8") (pintype "bidirectional"))
      (node (ref "R13") (pin "2") (pinfunction "2_2") (pintype "passive"))
    )
    (net (code "43") (name "/GPIO46") (class "Default")
      (node (ref "M1") (pin "H7") (pinfunction "IO/LED_BLUE_H7") (pintype "bidirectional"))
      (node (ref "TP11") (pin "1") (pintype "passive"))
    )
    (net (code "44") (name "/GPIO47") (class "Default")
      (node (ref "M1") (pin "F3") (pinfunction "IO/RMII_RXD0_F3") (pintype "bidirectional"))
      (node (ref "TP12") (pin "1") (pintype "passive"))
    )
    (net (code "45") (name "/GPIO48") (class "Default")
      (node (ref "M1") (pin "E3") (pinfunction "IO/RMII_RXD1_E3") (pintype "bidirectional"))
      (node (ref "TP13") (pin "1") (pintype "passive"))
    )
    (net (code "46") (name "/MTCK") (class "Default")
      (node (ref "M1") (pin "J2") (pinfunction "SWDCLK/TCK_J2") (pintype "input"))
    )
    (net (code "47") (name "/MTDI") (class "Default")
      (node (ref "M1") (pin "H1") (pinfunction "IO/TDI_H1") (pintype "bidirectional"))
    )
    (net (code "48") (name "/MTDO") (class "Default")
      (node (ref "M1") (pin "G1") (pinfunction "IO/TDO_G1") (pintype "bidirectional"))
    )
    (net (code "49") (name "/MTMS") (class "Default")
      (node (ref "M1") (pin "H2") (pinfunction "SWDIO/TMS_H2") (pintype "bidirectional"))
    )
    (net (code "50") (name "/P_IN") (class "Default")
      (node (ref "C3") (pin "1") (pinfunction "1_1") (pintype "passive"))
      (node (ref "D2") (pin "C") (pinfunction "Cathode_C") (pintype "passive"))
      (node (ref "D3") (pin "C") (pinfunction "Cathode_C") (pintype "passive"))
      (node (ref "R49") (pin "1") (pinfunction "1_1") (pintype "passive"))
      (node (ref "U1") (pin "1") (pinfunction "IN_1") (pintype "input"))
      (node (ref "U1") (pin "6") (pinfunction "IN_6") (pintype "input"))
    )
    (net (code "51") (name "/RESET") (class "Default")
      (node (ref "M1") (pin "J3") (pinfunction "nRESET_J3") (pintype "input"))
    )
    (net (code "52") (name "/RF_PIN") (class "Default")
      (node (ref "J1") (pin "1") (pinfunction "ANT_1") (pintype "passive"))
      (node (ref "M1") (pin "K9") (pinfunction "ANT1_K9") (pintype "passive"))
    )
    (net (code "53") (name "/USB_IOD_N") (class "Default")
      (node (ref "M1") (pin "D9") (pinfunction "D-_D9") (pintype "bidirectional"))
      (node (ref "R17") (pin "1") (pinfunction "1_1") (pintype "passive"))
    )
    (net (code "54") (name "/USB_IOD_P") (class "Default")
      (node (ref "M1") (pin "C9") (pinfunction "D+_C9") (pintype "bidirectional"))
      (node (ref "R10") (pin "2") (pinfunction "2_2") (pintype "passive"))
    )
    (net (code "55") (name "/USB_I_N") (class "Default")
      (node (ref "R14") (pin "2") (pinfunction "2_2") (pintype "passive"))
      (node (ref "U2") (pin "9") (pinfunction "USBDM_9") (pintype "input"))
    )
    (net (code "56") (name "/USB_I_P") (class "Default")
      (node (ref "R12") (pin "2") (pinfunction "2_2") (pintype "passive"))
      (node (ref "U2") (pin "8") (pinfunction "USBDP_8") (pintype "input"))
    )
    (net (code "57") (name "/USB_N") (class "Default")
      (node (ref "D4") (pin "1") (pinfunction "IO1_1") (pintype "passive"))
      (node (ref "J2") (pin "2") (pinfunction "D-_2") (pintype "bidirectional"))
      (node (ref "R14") (pin "1") (pinfunction "1_1") (pintype "passive"))
      (node (ref "R17") (pin "2") (pinfunction "2_2") (pintype "passive"))
      (node (ref "TP16") (pin "1") (pintype "passive"))
    )
    (net (code "58") (name "/USB_P") (class "Default")
      (node (ref "D4") (pin "2") (pinfunction "IO2_2") (pintype "passive"))
      (node (ref "J2") (pin "3") (pinfunction "D+_3") (pintype "bidirectional"))
      (node (ref "R10") (pin "1") (pinfunction "1_1") (pintype "passive"))
      (node (ref "R12") (pin "1") (pinfunction "1_1") (pintype "passive"))
      (node (ref "TP15") (pin "1") (pintype "passive"))
    )
    (net (code "59") (name "/VBUS_OUT") (class "Default")
      (node (ref "F1") (pin "2") (pinfunction "2_2") (pintype "passive"))
      (node (ref "J2") (pin "1") (pinfunction "VBUS_1") (pintype "power_in"))
    )
    (net (code "60") (name "/VDD_SPI") (class "Default")
      (node (ref "M1") (pin "J1") (pinfunction "VDD_SPI_J1") (pintype "passive"))
      (node (ref "TP1") (pin "1") (pintype "passive"))
    )
    (net (code "61") (name "/XTAL_32K_N") (class "Default")
      (node (ref "C11") (pin "1") (pinfunction "1_1") (pintype "passive"))
      (node (ref "M1") (pin "B6") (pinfunction "IO/XL2(32kHz_IN)_B6") (pintype "bidirectional"))
      (node (ref "X1") (pin "2") (pintype "passive"))
    )
    (net (code "62") (name "/XTAL_32K_P") (class "Default")
      (node (ref "C10") (pin "1") (pinfunction "1_1") (pintype "passive"))
      (node (ref "M1") (pin "C6") (pinfunction "IO/XL1_C6") (pintype "bidirectional"))
      (node (ref "X1") (pin "1") (pintype "passive"))
    )
    (net (code "68") (name "3V3") (class "Default")
      (node (ref "C1") (pin "1") (pinfunction "1_1") (pintype "passive"))
      (node (ref "C2") (pin "1") (pinfunction "1_1") (pintype "passive"))
      (node (ref "C4") (pin "1") (pinfunction "1_1") (pintype "passive"))
      (node (ref "C5") (pin "1") (pinfunction "1_1") (pintype "passive"))
      (node (ref "C8") (pin "1") (pinfunction "1_1") (pintype "passive"))
      (node (ref "C9") (pin "1") (pinfunction "1_1") (pintype "passive"))
      (node (ref "D1") (pin "2") (pinfunction "A_2") (pintype "passive"))
      (node (ref "M1") (pin "A7") (pinfunction "VDD_A7") (pintype "power_in"))
      (node (ref "M1") (pin "A8") (pinfunction "VDDH_A8") (pintype "power_in"))
      (node (ref "M1") (pin "B7") (pinfunction "VDD_B7") (pintype "power_in"))
      (node (ref "R3") (pin "1") (pinfunction "1_1") (pintype "passive"))
      (node (ref "RGB1") (pin "4") (pinfunction "A_4") (pintype "passive"))
      (node (ref "U1") (pin "5") (pinfunction "OUT_5") (pintype "power_in"))
      (node (ref "U2") (pin "10") (pinfunction "3V3OUT_10") (pintype "input"))
      (node (ref "U2") (pin "11") (pinfunction "~{RESET}_11") (pintype "input"))
      (node (ref "U2") (pin "12") (pinfunction "VCC_12") (pintype "power_in"))
      (node (ref "U2") (pin "20") (pinfunction "VCCIO_20") (pintype "power_in"))
    )
    (net (code "69") (name "GND") (class "Default")
      (node (ref "C1") (pin "2") (pinfunction "2_2") (pintype "passive"))
      (node (ref "C10") (pin "2") (pinfunction "2_2") (pintype "passive"))
      (node (ref "C11") (pin "2") (pinfunction "2_2") (pintype "passive"))
      (node (ref "C2") (pin "2") (pinfunction "2_2") (pintype "passive"))
      (node (ref "C3") (pin "2") (pinfunction "2_2") (pintype "passive"))
      (node (ref "C4") (pin "2") (pinfunction "2_2") (pintype "passive"))
      (node (ref "C5") (pin "2") (pinfunction "2_2") (pintype "passive"))
      (node (ref "C6") (pin "2") (pinfunction "2_2") (pintype "passive"))
      (node (ref "C7") (pin "2") (pinfunction "2_2") (pintype "passive"))
      (node (ref "C8") (pin "2") (pinfunction "2_2") (pintype "passive"))
      (node (ref "C9") (pin "2") (pinfunction "2_2") (pintype "passive"))
      (node (ref "D4") (pin "3") (pinfunction "GND_3") (pintype "power_in"))
      (node (ref "J1") (pin "2") (pinfunction "2_2") (pintype "power_in"))
      (node (ref "J2") (pin "4") (pinfunction "GND_4") (pintype "power_in"))
      (node (ref "M1") (pin "A1") (pinfunction "VSS_A1") (pintype "power_in"))
      (node (ref "M1") (pin "A9") (pinfunction "VSS_A9") (pintype "power_in"))
      (node (ref "M1") (pin "B2") (pinfunction "VSS_B2") (pintype "power_in"))
      (node (ref "M1") (pin "B8") (pinfunction "VSS_B8") (pintype "power_in"))
      (node (ref "M1") (pin "E4") (pinfunction "VSS_E4") (pintype "power_in"))
      (node (ref "M1") (pin "E5") (pinfunction "VSS_E5") (pintype "power_in"))
      (node (ref "M1") (pin "F4") (pinfunction "VSS_F4") (pintype "power_in"))
      (node (ref "M1") (pin "F5") (pinfunction "VSS_F5") (pintype "power_in"))
      (node (ref "M1") (pin "K2") (pinfunction "VSS_K2") (pintype "power_in"))
      (node (ref "M1") (pin "K3") (pinfunction "VSS_K3") (pintype "power_in"))
      (node (ref "M1") (pin "K5") (pinfunction "VSS_K5") (pintype "power_in"))
      (node (ref "M1") (pin "K7") (pinfunction "VSS_K7") (pintype "power_in"))
      (node (ref "M1") (pin "K8") (pinfunction "VSS_K8") (pintype "power_in"))
      (node (ref "M1") (pin "L1") (pinfunction "VSS_L1") (pintype "power_in"))
      (node (ref "M1") (pin "L9") (pinfunction "VSS_L9") (pintype "power_in"))
      (node (ref "M1") (pin "M1") (pinfunction "VSS_M1") (pintype "power_in"))
      (node (ref "M1") (pin "M2") (pinfunction "VSS_M2") (pintype "power_in"))
      (node (ref "M1") (pin "M8") (pinfunction "VSS_M8") (pintype "power_in"))
      (node (ref "M1") (pin "M9") (pinfunction "VSS_M9") (pintype "power_in"))
      (node (ref "R1") (pin "2") (pinfunction "2_2") (pintype "passive"))
      (node (ref "R5") (pin "1") (pinfunction "1_1") (pintype "passive"))
      (node (ref "R50") (pin "1") (pinfunction "1_1") (pintype "passive"))
      (node (ref "R6") (pin "1") (pinfunction "1_1") (pintype "passive"))
      (node (ref "TP14") (pin "1") (pintype "passive"))
      (node (ref "U1") (pin "2") (pinfunction "GND_2") (pintype "power_in"))
      (node (ref "U2") (pin "13") (pinfunction "GND_13") (pintype "power_in"))
      (node (ref "U2") (pin "21") (pinfunction "GND_21") (pintype "power_in"))
      (node (ref "U2") (pin "3") (pinfunction "GND_3") (pintype "power_in"))
    )
    (net (code "70") (name "Net-(D1-C)") (class "Default")
      (node (ref "D1") (pin "1") (pinfunction "C_1") (pintype "passive"))
      (node (ref "R1") (pin "1") (pinfunction "1_1") (pintype "passive"))
    )
    (net (code "71") (name "Net-(RGB1-B)") (class "Default")
      (node (ref "R2") (pin "1") (pinfunction "1_1") (pintype "passive"))
      (node (ref "RGB1") (pin "3") (pinfunction "B_3") (pintype "passive"))
    )
    (net (code "72") (name "Net-(RGB1-G)") (class "Default")
      (node (ref "R4") (pin "1") (pinfunction "1_1") (pintype "passive"))
      (node (ref "RGB1") (pin "2") (pinfunction "G_2") (pintype "passive"))
    )
    (net (code "73") (name "Net-(RGB1-R)") (class "Default")
      (node (ref "R7") (pin "1") (pinfunction "1_1") (pintype "passive"))
      (node (ref "RGB1") (pin "1") (pinfunction "R_1") (pintype "passive"))
    )
    (net (code "74") (name "Net-(U1-ADJ)") (class "Default")
      (node (ref "R3") (pin "2") (pinfunction "2_2") (pintype "passive"))
      (node (ref "R5") (pin "2") (pinfunction "2_2") (pintype "passive"))
      (node (ref "R6") (pin "2") (pinfunction "2_2") (pintype "passive"))
      (node (ref "U1") (pin "4") (pinfunction "ADJ_4") (pintype "input"))
    )
    (net (code "75") (name "Net-(U1-EN)") (class "Default")
      (node (ref "R49") (pin "2") (pinfunction "2_2") (pintype "passive"))
      (node (ref "R50") (pin "2") (pinfunction "2_2") (pintype "passive"))
      (node (ref "U1") (pin "3") (pinfunction "EN_3") (pintype "input"))
    )
    (net (code "76") (name "Net-(U2-RXD)") (class "Default")
      (node (ref "R9") (pin "1") (pinfunction "1_1") (pintype "passive"))
      (node (ref "U2") (pin "1") (pinfunction "RXD_1") (pintype "input"))
    )
    (net (code "77") (name "Net-(U2-TXD)") (class "Default")
      (node (ref "R8") (pin "1") (pinfunction "1_1") (pintype "passive"))
      (node (ref "U2") (pin "17") (pinfunction "TXD_17") (pintype "output"))
    )
    (net (code "78") (name "Net-(U2-~{CTS})") (class "Default")
      (node (ref "R13") (pin "1") (pinfunction "1_1") (pintype "passive"))
      (node (ref "U2") (pin "6") (pinfunction "~{CTS}_6") (pintype "input"))
    )
    (net (code "79") (name "Net-(U2-~{DSR})") (class "Default")
      (node (ref "R16") (pin "1") (pinfunction "1_1") (pintype "passive"))
      (node (ref "U2") (pin "4") (pinfunction "~{DSR}_4") (pintype "input"))
    )
    (net (code "80") (name "Net-(U2-~{DTR})") (class "Default")
      (node (ref "R15") (pin "1") (pinfunction "1_1") (pintype "passive"))
      (node (ref "U2") (pin "18") (pinfunction "~{DTR}_18") (pintype "output"))
    )
    (net (code "81") (name "Net-(U2-~{RTS})") (class "Default")
      (node (ref "R11") (pin "1") (pinfunction "1_1") (pintype "passive"))
      (node (ref "U2") (pin "19") (pinfunction "~{RTS}_19") (pintype "output"))
    )
    (net (code "82") (name "VBUS") (class "Default")
      (node (ref "C6") (pin "1") (pinfunction "1_1") (pintype "passive"))
      (node (ref "C7") (pin "1") (pinfunction "1_1") (pintype "passive"))
      (node (ref "D3") (pin "A") (pinfunction "Anode_A") (pintype "passive"))
      (node (ref "D4") (pin "5") (pinfunction "Vcc_5") (pintype "power_in"))
      (node (ref "F1") (pin "1") (pinfunction "1_1") (pintype "passive"))
    )
    (net (code "83") (name "VIN") (class "Default")
      (node (ref "D2") (pin "A") (pinfunction "Anode_A") (pintype "passive"))
    )
    (net (code "84") (name "unconnected-(D4-IO3-Pad4)") (class "Default")
      (node (ref "D4") (pin "4") (pinfunction "IO3_4") (pintype "passive+no_connect"))
    )
    (net (code "85") (name "unconnected-(M1-ANT2-PadK1)") (class "Default")
      (node (ref "M1") (pin "K1") (pinfunction "ANT2_K1") (pintype "passive+no_connect"))
    )
    (net (code "86") (name "unconnected-(M1-IO-PadA4)") (class "Default")
      (node (ref "M1") (pin "A4") (pinfunction "IO_A4") (pintype "bidirectional+no_connect"))
    )
    (net (code "87") (name "unconnected-(M1-IO-PadD7)") (class "Default")
      (node (ref "M1") (pin "D7") (pinfunction "IO_D7") (pintype "bidirectional+no_connect"))
    )
    (net (code "88") (name "unconnected-(M1-IO-PadJ4)") (class "Default")
      (node (ref "M1") (pin "J4") (pinfunction "IO_J4") (pintype "bidirectional+no_connect"))
    )
    (net (code "89") (name "unconnected-(M1-IO-PadJ5)") (class "Default")
      (node (ref "M1") (pin "J5") (pinfunction "IO_J5") (pintype "bidirectional+no_connect"))
    )
    (net (code "90") (name "unconnected-(M1-IO{slash}NFC1-PadC5)") (class "Default")
      (node (ref "M1") (pin "C5") (pinfunction "IO/NFC1_C5") (pintype "bidirectional+no_connect"))
    )
    (net (code "91") (name "unconnected-(M1-IO{slash}NFC2-PadB5)") (class "Default")
      (node (ref "M1") (pin "B5") (pinfunction "IO/NFC2_B5") (pintype "bidirectional+no_connect"))
    )
    (net (code "92") (name "unconnected-(M1-IO{slash}RF_CTRL1{slash}CTX-PadG5)") (class "Default")
      (node (ref "M1") (pin "G5") (pinfunction "IO/RF_CTRL1/CTX_G5") (pintype "bidirectional+no_connect"))
    )
    (net (code "93") (name "unconnected-(M1-IO{slash}RF_CTRL2{slash}CRX-PadG7)") (class "Default")
      (node (ref "M1") (pin "G7") (pinfunction "IO/RF_CTRL2/CRX_G7") (pintype "bidirectional+no_connect"))
    )
    (net (code "94") (name "unconnected-(M1-IO{slash}RMII_CLK-PadG4)") (class "Default")
      (node (ref "M1") (pin "G4") (pinfunction "IO/RMII_CLK_G4") (pintype "bidirectional+no_connect"))
    )
    (net (code "95") (name "unconnected-(M1-IO{slash}RMII_CRS-PadJ7)") (class "Default")
      (node (ref "M1") (pin "J7") (pinfunction "IO/RMII_CRS_J7") (pintype "bidirectional+no_connect"))
    )
    (net (code "96") (name "unconnected-(M1-VBUS-PadB9)") (class "Default")
      (node (ref "M1") (pin "B9") (pinfunction "VBUS_B9") (pintype "power_in+no_connect"))
    )
    (net (code "97") (name "unconnected-(U2-CBUS0-Pad15)") (class "Default")
      (node (ref "U2") (pin "15") (pinfunction "CBUS0_15") (pintype "bidirectional+no_connect"))
    )
    (net (code "98") (name "unconnected-(U2-CBUS1-Pad14)") (class "Default")
      (node (ref "U2") (pin "14") (pinfunction "CBUS1_14") (pintype "bidirectional+no_connect"))
    )
    (net (code "99") (name "unconnected-(U2-CBUS2-Pad7)") (class "Default")
      (node (ref "U2") (pin "7") (pinfunction "CBUS2_7") (pintype "bidirectional+no_connect"))
    )
    (net (code "100") (name "unconnected-(U2-CBUS3-Pad16)") (class "Default")
      (node (ref "U2") (pin "16") (pinfunction "CBUS3_16") (pintype "bidirectional+no_connect"))
    )
    (net (code "101") (name "unconnected-(U2-~{DCD}-Pad5)") (class "Default")
      (node (ref "U2") (pin "5") (pinfunction "~{DCD}_5") (pintype "input+no_connect"))
    )
    (net (code "102") (name "unconnected-(U2-~{RI}-Pad2)") (class "Default")
      (node (ref "U2") (pin "2") (pinfunction "~{RI}_2") (pintype "input+no_connect"))
    )
  )
)
